# ACCIC.net
KiCad netlist of a schematic drawn in Altium Designer
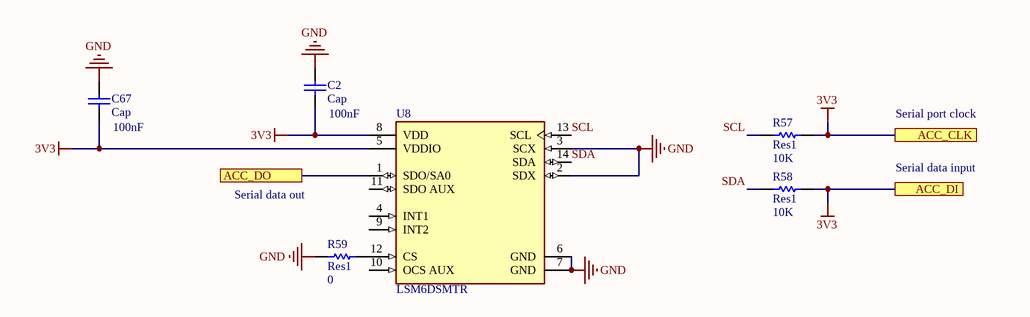
[diagram p0: ACCIC.SchDoc]

(export (version "E")
  (design (tool "Eeschema 10.0.6"))
  (components
    (comp (ref "C2")
      (value "Cap")
      (footprint "0402")
      (description "Capacitor")
      (fields (field (name "ALTIUM_VALUE") "100nF") (field (name "PUBLISHER") "Altium Limited"))
      (libsource (lib "Miscellaneous Devices") (part "Cap"))
    )
    (comp (ref "C67")
      (value "Cap")
      (footprint "0402")
      (description "Capacitor")
      (fields (field (name "ALTIUM_VALUE") "100nF") (field (name "PUBLISHER") "Altium Limited"))
      (libsource (lib "Miscellaneous Devices") (part "Cap"))
    )
    (comp (ref "R57")
      (value "Res1")
      (footprint "0402")
      (description "Resistor")
      (fields (field (name "ALTIUM_VALUE") "10K") (field (name "PUBLISHER") "Altium Limited"))
      (libsource (lib "Miscellaneous Devices") (part "Res1"))
    )
    (comp (ref "R58")
      (value "Res1")
      (footprint "0402")
      (description "Resistor")
      (fields (field (name "ALTIUM_VALUE") "10K") (field (name "PUBLISHER") "Altium Limited"))
      (libsource (lib "Miscellaneous Devices") (part "Res1"))
    )
    (comp (ref "R59")
      (value "Res1")
      (footprint "0402")
      (description "Resistor")
      (fields (field (name "ALTIUM_VALUE") "0") (field (name "PUBLISHER") "Altium Limited"))
      (libsource (lib "Miscellaneous Devices") (part "Res1"))
    )
    (comp (ref "U8")
      (value "LSM6DSMTR")
      (footprint "FP-LGA-14L-DM00249496-MFG")
      (description "IMU ACCEL/GYRO I2C/SPI 14LGA")
      (fields
        (field (name "OCTOPART") "https://octopart.com/lsm6dsmtr-stmicroelectronics-66358194")
        (field (name "MANUFACTURER") "STMicroelectronics")
      )
      (libsource (lib "Altium Content Vault") (part "dd82ae232bae541fa9c740d21cb9072"))
    )
  )
  (nets
    (net (code "1") (name "/ACC_DO") (class "Default")
      (node (ref "U8") (pin "1") (pinfunction "SDO/SA0_1") (pintype "bidirectional"))
    )
    (net (code "2") (name "/SCL") (class "Default")
      (node (ref "R57") (pin "1") (pinfunction "1_1") (pintype "passive"))
      (node (ref "U8") (pin "13") (pinfunction "SCL_13") (pintype "input"))
    )
    (net (code "3") (name "/SDA") (class "Default")
      (node (ref "R58") (pin "1") (pinfunction "1_1") (pintype "passive"))
      (node (ref "U8") (pin "14") (pinfunction "SDA_14") (pintype "bidirectional"))
    )
    (net (code "4") (name "3V3") (class "Default")
      (node (ref "C2") (pin "2") (pinfunction "2_2") (pintype "passive"))
      (node (ref "C67") (pin "2") (pinfunction "2_2") (pintype "passive"))
      (node (ref "R57") (pin "2") (pinfunction "2_2") (pintype "passive"))
      (node (ref "R58") (pin "2") (pinfunction "2_2") (pintype "passive"))
      (node (ref "U8") (pin "5") (pinfunction "VDDIO_5") (pintype "power_in"))
      (node (ref "U8") (pin "8") (pinfunction "VDD_8") (pintype "power_in"))
    )
    (net (code "5") (name "GND") (class "Default")
      (node (ref "C2") (pin "1") (pinfunction "1_1") (pintype "passive"))
      (node (ref "C67") (pin "1") (pinfunction "1_1") (pintype "passive"))
      (node (ref "R59") (pin "1") (pinfunction "1_1") (pintype "passive"))
      (node (ref "U8") (pin "2") (pinfunction "SDX_2") (pintype "bidirectional"))
      (node (ref "U8") (pin "3") (pinfunction "SCX_3") (pintype "input"))
      (node (ref "U8") (pin "6") (pinfunction "GND_6") (pintype "power_in"))
      (node (ref "U8") (pin "7") (pinfunction "GND_7") (pintype "power_in"))
    )
    (net (code "6") (name "Net-(U8-CS)") (class "Default")
      (node (ref "R59") (pin "2") (pinfunction "2_2") (pintype "passive"))
      (node (ref "U8") (pin "12") (pinfunction "CS_12") (pintype "input"))
    )
    (net (code "7") (name "unconnected-(U8-INT1-Pad4)") (class "Default")
      (node (ref "U8") (pin "4") (pinfunction "INT1_4") (pintype "input"))
    )
    (net (code "8") (name "unconnected-(U8-INT2-Pad9)") (class "Default")
      (node (ref "U8") (pin "9") (pinfunction "INT2_9") (pintype "input"))
    )
    (net (code "9") (name "unconnected-(U8-OCS_AUX-Pad10)") (class "Default")
      (node (ref "U8") (pin "10") (pinfunction "OCS_AUX_10") (pintype "input"))
    )
    (net (code "10") (name "unconnected-(U8-SDO_AUX-Pad11)") (class "Default")
      (node (ref "U8") (pin "11") (pinfunction "SDO_AUX_11") (pintype "bidirectional"))
    )
  )
)
